# Volt_Metter_SCH.net
KiCad netlist of a schematic drawn in Altium Designer
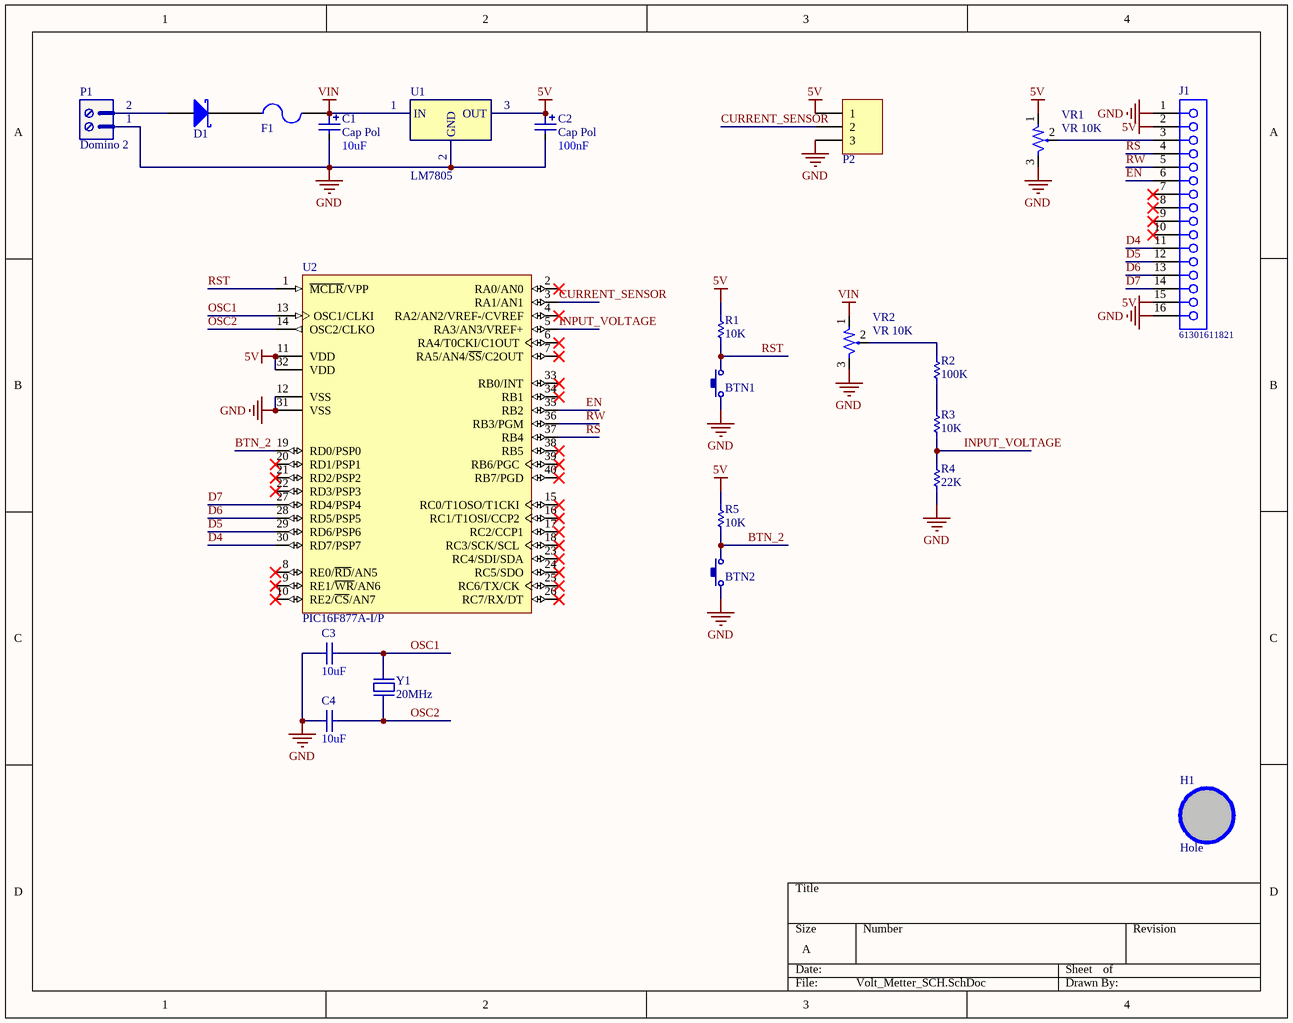
[diagram p0: Volt_Metter_SCH.SchDoc]

(export (version "E")
  (design (tool "Eeschema 10.0.6"))
  (components
    (comp (ref "BTN1")
      (value "Button")
      (footprint "Button")
      (libsource (lib "DeltaCross_Lib") (part "Button"))
    )
    (comp (ref "BTN2")
      (value "Button")
      (footprint "Button")
      (libsource (lib "DeltaCross_Lib") (part "Button"))
    )
    (comp (ref "C1")
      (value "Cap Pol")
      (footprint "CP1/2.5")
      (description "Polarized Capacitor (Radial)")
      (fields (field (name "ALTIUM_VALUE") "10uF"))
      (libsource (lib "DeltaCross_Lib") (part "Cap Pol"))
    )
    (comp (ref "C2")
      (value "Cap Pol")
      (footprint "CP1/2.5")
      (description "Polarized Capacitor (Radial)")
      (fields (field (name "ALTIUM_VALUE") "100nF"))
      (libsource (lib "DeltaCross_Lib") (part "Cap Pol"))
    )
    (comp (ref "C3")
      (value "10uF")
      (footprint "CAP-SM-0805")
      (description "Capacitor")
      (fields (field (name "Comment") "Cap Non-Pol SMD"))
      (libsource (lib "DeltaCross_Lib") (part "Cap Non-Pol SMD"))
    )
    (comp (ref "C4")
      (value "10uF")
      (footprint "CAP-SM-0805")
      (description "Capacitor")
      (fields (field (name "Comment") "Cap Non-Pol SMD"))
      (libsource (lib "DeltaCross_Lib") (part "Cap Non-Pol SMD"))
    )
    (comp (ref "D1")
      (value "D Schottky")
      (footprint "SS34")
      (description "Schottky Diode")
      (fields (field (name "PUBLISHER") "Altium Limited"))
      (libsource (lib "PIF_Library") (part "D Schottky"))
    )
    (comp (ref "F1") (value "Fuse") (footprint "FUSE SMD") (libsource (lib "PIF_Library") (part "Fuse")))
    (comp (ref "H1")
      (value "Hole")
      (footprint "LO KHOAN 3MM")
      (description "Hole 3mm")
      (libsource (lib "DeltaCross_Lib") (part "Hole"))
    )
    (comp (ref "J1")
      (value "61301611821")
      (footprint "61301611821")
      (description "WR-PHD Socket Header, THT, pitch 2.54mm, Single Row, Vertical, 16p")
      (fields (field (name "MANUFACTURER") "Wurth Elektronik"))
      (libsource (lib "Altium_WR-PHD (rev20a)") (part "61301611821"))
    )
    (comp (ref "P1")
      (value "Domino 2")
      (footprint "DOMINO 2- 5mm")
      (description "Domino, 2-Pin")
      (fields (field (name "PUBLISHER") "Altium Limited"))
      (libsource (lib "DeltaCross_Lib") (part "Domino 2"))
    )
    (comp (ref "P2")
      (value "Header 3")
      (footprint "JP3")
      (description "Header, 3-Pin")
      (fields (field (name "PUBLISHER") "Altium Limited"))
      (libsource (lib "PIF_Library") (part "Header 3"))
    )
    (comp (ref "R1")
      (value "10K")
      (footprint "RES-SM-0805")
      (fields (field (name "Comment") "Resistor 1/4W"))
      (libsource (lib "DeltaCross_Lib") (part "RES"))
    )
    (comp (ref "R2")
      (value "100K")
      (footprint "RES-SM-0805")
      (fields (field (name "Comment") "Resistor 1/4W"))
      (libsource (lib "DeltaCross_Lib") (part "RES"))
    )
    (comp (ref "R3")
      (value "10K")
      (footprint "RES-SM-0805")
      (fields (field (name "Comment") "Resistor 1/4W"))
      (libsource (lib "DeltaCross_Lib") (part "RES"))
    )
    (comp (ref "R4")
      (value "22K")
      (footprint "RES-SM-0805")
      (fields (field (name "Comment") "Resistor 1/4W"))
      (libsource (lib "DeltaCross_Lib") (part "RES"))
    )
    (comp (ref "R5")
      (value "10K")
      (footprint "RES-SM-0805")
      (fields (field (name "Comment") "Resistor 1/4W"))
      (libsource (lib "DeltaCross_Lib") (part "RES"))
    )
    (comp (ref "U1")
      (value "LM7805")
      (footprint "QTO-220")
      (description "Positive Voltage Regulator")
      (libsource (lib "DeltaCross_Lib") (part "LM7805"))
    )
    (comp (ref "U2")
      (value "PIC16F877A-I/P")
      (footprint "PDIP600-P40")
      (libsource (lib "DeltaCross_Lib") (part "PIC16F877A-I/P"))
    )
    (comp (ref "VR1")
      (value "VR 10K")
      (footprint "Varistor 1")
      (description "Var Resistor")
      (fields (field (name "Comment") "10K"))
      (libsource (lib "PIF_Library") (part "Var Resistor"))
    )
    (comp (ref "VR2")
      (value "VR 10K")
      (footprint "Varistor 1")
      (description "Var Resistor")
      (fields (field (name "Comment") "10K"))
      (libsource (lib "PIF_Library") (part "Var Resistor"))
    )
    (comp (ref "Y1")
      (value "20MHz")
      (footprint "XT2")
      (description "Crystal For all Crystal 2pin")
      (libsource (lib "DeltaCross_Lib") (part "XTAL"))
    )
  )
  (nets
    (net (code "1") (name "/BTN_2") (class "Default")
      (node (ref "BTN2") (pin "2") (pintype "passive"))
      (node (ref "R5") (pin "1") (pintype "passive"))
      (node (ref "U2") (pin "19") (pinfunction "RD0/PSP0_19") (pintype "bidirectional"))
    )
    (net (code "2") (name "/CURRENT_SENSOR") (class "Default")
      (node (ref "P2") (pin "2") (pinfunction "2_2") (pintype "passive"))
      (node (ref "U2") (pin "3") (pinfunction "RA1/AN1_3") (pintype "bidirectional"))
    )
    (net (code "3") (name "/D4") (class "Default")
      (node (ref "J1") (pin "11") (pinfunction "11_11") (pintype "passive"))
      (node (ref "U2") (pin "30") (pinfunction "RD7/PSP7_30") (pintype "bidirectional"))
    )
    (net (code "4") (name "/D5") (class "Default")
      (node (ref "J1") (pin "12") (pinfunction "12_12") (pintype "passive"))
      (node (ref "U2") (pin "29") (pinfunction "RD6/PSP6_29") (pintype "bidirectional"))
    )
    (net (code "5") (name "/D6") (class "Default")
      (node (ref "J1") (pin "13") (pinfunction "13_13") (pintype "passive"))
      (node (ref "U2") (pin "28") (pinfunction "RD5/PSP5_28") (pintype "bidirectional"))
    )
    (net (code "6") (name "/D7") (class "Default")
      (node (ref "J1") (pin "14") (pinfunction "14_14") (pintype "passive"))
      (node (ref "U2") (pin "27") (pinfunction "RD4/PSP4_27") (pintype "bidirectional"))
    )
    (net (code "7") (name "/EN") (class "Default")
      (node (ref "J1") (pin "6") (pinfunction "6_6") (pintype "passive"))
      (node (ref "U2") (pin "35") (pinfunction "RB2_35") (pintype "bidirectional"))
    )
    (net (code "8") (name "/INPUT_VOLTAGE") (class "Default")
      (node (ref "R3") (pin "1") (pintype "passive"))
      (node (ref "R4") (pin "2") (pintype "passive"))
      (node (ref "U2") (pin "5") (pinfunction "RA3/AN3/VREF+_5") (pintype "bidirectional"))
    )
    (net (code "9") (name "/OSC1") (class "Default")
      (node (ref "C3") (pin "2") (pinfunction "2_2") (pintype "passive"))
      (node (ref "U2") (pin "13") (pinfunction "OSC1/CLKI_13") (pintype "input"))
      (node (ref "Y1") (pin "2") (pinfunction "2_2") (pintype "passive"))
    )
    (net (code "10") (name "/OSC2") (class "Default")
      (node (ref "C4") (pin "2") (pinfunction "2_2") (pintype "passive"))
      (node (ref "U2") (pin "14") (pinfunction "OSC2/CLKO_14") (pintype "output"))
      (node (ref "Y1") (pin "1") (pinfunction "1_1") (pintype "passive"))
    )
    (net (code "11") (name "/RS") (class "Default")
      (node (ref "J1") (pin "4") (pinfunction "4_4") (pintype "passive"))
      (node (ref "U2") (pin "37") (pinfunction "RB4_37") (pintype "bidirectional"))
    )
    (net (code "12") (name "/RST") (class "Default")
      (node (ref "BTN1") (pin "2") (pintype "passive"))
      (node (ref "R1") (pin "1") (pintype "passive"))
      (node (ref "U2") (pin "1") (pinfunction "~{MCLR}/VPP_1") (pintype "input"))
    )
    (net (code "13") (name "/RW") (class "Default")
      (node (ref "J1") (pin "5") (pinfunction "5_5") (pintype "passive"))
      (node (ref "U2") (pin "36") (pinfunction "RB3/PGM_36") (pintype "bidirectional"))
    )
    (net (code "14") (name "5V") (class "Default")
      (node (ref "C2") (pin "1") (pinfunction "1_1") (pintype "passive"))
      (node (ref "J1") (pin "15") (pinfunction "15_15") (pintype "passive"))
      (node (ref "J1") (pin "2") (pinfunction "2_2") (pintype "passive"))
      (node (ref "P2") (pin "1") (pinfunction "1_1") (pintype "passive"))
      (node (ref "R1") (pin "2") (pintype "passive"))
      (node (ref "R5") (pin "2") (pintype "passive"))
      (node (ref "U1") (pin "3") (pinfunction "OUT_3") (pintype "power_in"))
      (node (ref "U2") (pin "11") (pinfunction "VDD_11") (pintype "power_in"))
      (node (ref "U2") (pin "32") (pinfunction "VDD_32") (pintype "power_in"))
      (node (ref "VR1") (pin "1") (pinfunction "1_1") (pintype "passive"))
    )
    (net (code "15") (name "GND") (class "Default")
      (node (ref "BTN1") (pin "1") (pintype "passive"))
      (node (ref "BTN2") (pin "1") (pintype "passive"))
      (node (ref "C1") (pin "2") (pinfunction "2_2") (pintype "passive"))
      (node (ref "C2") (pin "2") (pinfunction "2_2") (pintype "passive"))
      (node (ref "C3") (pin "1") (pinfunction "1_1") (pintype "passive"))
      (node (ref "C4") (pin "1") (pinfunction "1_1") (pintype "passive"))
      (node (ref "J1") (pin "1") (pinfunction "1_1") (pintype "passive"))
      (node (ref "J1") (pin "16") (pinfunction "16_16") (pintype "passive"))
      (node (ref "P1") (pin "1") (pinfunction "1_1") (pintype "passive"))
      (node (ref "P2") (pin "3") (pinfunction "3_3") (pintype "passive"))
      (node (ref "R4") (pin "1") (pintype "passive"))
      (node (ref "U1") (pin "2") (pinfunction "GND_2") (pintype "power_in"))
      (node (ref "U2") (pin "12") (pinfunction "VSS_12") (pintype "power_in"))
      (node (ref "U2") (pin "31") (pinfunction "VSS_31") (pintype "power_in"))
      (node (ref "VR1") (pin "3") (pinfunction "3_3") (pintype "passive"))
      (node (ref "VR2") (pin "3") (pinfunction "3_3") (pintype "passive"))
    )
    (net (code "16") (name "Net-(D1-A)") (class "Default")
      (node (ref "D1") (pin "1") (pinfunction "A_1") (pintype "passive"))
      (node (ref "P1") (pin "2") (pinfunction "2_2") (pintype "passive"))
    )
    (net (code "17") (name "Net-(D1-K)") (class "Default")
      (node (ref "D1") (pin "2") (pinfunction "K_2") (pintype "passive"))
      (node (ref "F1") (pin "1") (pinfunction "1_1") (pintype "passive"))
    )
    (net (code "18") (name "Net-(J1-Pad3)") (class "Default")
      (node (ref "J1") (pin "3") (pinfunction "3_3") (pintype "passive"))
      (node (ref "VR1") (pin "2") (pinfunction "2_2") (pintype "passive"))
    )
    (net (code "19") (name "Net-(R2-Pad1)") (class "Default")
      (node (ref "R2") (pin "1") (pintype "passive"))
      (node (ref "R3") (pin "2") (pintype "passive"))
    )
    (net (code "20") (name "Net-(R2-Pad2)") (class "Default")
      (node (ref "R2") (pin "2") (pintype "passive"))
      (node (ref "VR2") (pin "2") (pinfunction "2_2") (pintype "passive"))
    )
    (net (code "21") (name "VIN") (class "Default")
      (node (ref "C1") (pin "1") (pinfunction "1_1") (pintype "passive"))
      (node (ref "F1") (pin "2") (pinfunction "2_2") (pintype "passive"))
      (node (ref "U1") (pin "1") (pinfunction "IN_1") (pintype "power_in"))
      (node (ref "VR2") (pin "1") (pinfunction "1_1") (pintype "passive"))
    )
    (net (code "22") (name "unconnected-(H1-Pad1)") (class "Default")
      (node (ref "H1") (pin "1") (pinfunction "1_1") (pintype "passive"))
    )
    (net (code "23") (name "unconnected-(J1-Pad7)") (class "Default")
      (node (ref "J1") (pin "7") (pinfunction "7_7") (pintype "passive+no_connect"))
    )
    (net (code "24") (name "unconnected-(J1-Pad8)") (class "Default")
      (node (ref "J1") (pin "8") (pinfunction "8_8") (pintype "passive+no_connect"))
    )
    (net (code "25") (name "unconnected-(J1-Pad9)") (class "Default")
      (node (ref "J1") (pin "9") (pinfunction "9_9") (pintype "passive+no_connect"))
    )
    (net (code "26") (name "unconnected-(J1-Pad10)") (class "Default")
      (node (ref "J1") (pin "10") (pinfunction "10_10") (pintype "passive+no_connect"))
    )
    (net (code "27") (name "unconnected-(U2-RA0{slash}AN0-Pad2)") (class "Default")
      (node (ref "U2") (pin "2") (pinfunction "RA0/AN0_2") (pintype "bidirectional+no_connect"))
    )
    (net (code "28") (name "unconnected-(U2-RA2{slash}AN2{slash}VREF-{slash}CVREF-Pad4)") (class "Default")
      (node (ref "U2") (pin "4") (pinfunction "RA2/AN2/VREF-/CVREF_4") (pintype "bidirectional+no_connect"))
    )
    (net (code "29") (name "unconnected-(U2-RA4{slash}T0CKI{slash}C1OUT-Pad6)") (class "Default")
      (node (ref "U2") (pin "6") (pinfunction "RA4/T0CKI/C1OUT_6") (pintype "bidirectional+no_connect"))
    )
    (net (code "30") (name "unconnected-(U2-RA5{slash}AN4{slash}~{SS}{slash}C2OUT-Pad7)") (class "Default")
      (node (ref "U2") (pin "7") (pinfunction "RA5/AN4/~{SS}/C2OUT_7") (pintype "bidirectional+no_connect"))
    )
    (net (code "31") (name "unconnected-(U2-RB0{slash}INT-Pad33)") (class "Default")
      (node (ref "U2") (pin "33") (pinfunction "RB0/INT_33") (pintype "bidirectional+no_connect"))
    )
    (net (code "32") (name "unconnected-(U2-RB1-Pad34)") (class "Default")
      (node (ref "U2") (pin "34") (pinfunction "RB1_34") (pintype "bidirectional+no_connect"))
    )
    (net (code "33") (name "unconnected-(U2-RB5-Pad38)") (class "Default")
      (node (ref "U2") (pin "38") (pinfunction "RB5_38") (pintype "bidirectional+no_connect"))
    )
    (net (code "34") (name "unconnected-(U2-RB6{slash}PGC-Pad39)") (class "Default")
      (node (ref "U2") (pin "39") (pinfunction "RB6/PGC_39") (pintype "bidirectional+no_connect"))
    )
    (net (code "35") (name "unconnected-(U2-RB7{slash}PGD-Pad40)") (class "Default")
      (node (ref "U2") (pin "40") (pinfunction "RB7/PGD_40") (pintype "bidirectional+no_connect"))
    )
    (net (code "36") (name "unconnected-(U2-RC0{slash}T1OSO{slash}T1CKI-Pad15)") (class "Default")
      (node (ref "U2") (pin "15") (pinfunction "RC0/T1OSO/T1CKI_15") (pintype "bidirectional+no_connect"))
    )
    (net (code "37") (name "unconnected-(U2-RC1{slash}T1OSI{slash}CCP2-Pad16)") (class "Default")
      (node (ref "U2") (pin "16") (pinfunction "RC1/T1OSI/CCP2_16") (pintype "bidirectional+no_connect"))
    )
    (net (code "38") (name "unconnected-(U2-RC2{slash}CCP1-Pad17)") (class "Default")
      (node (ref "U2") (pin "17") (pinfunction "RC2/CCP1_17") (pintype "bidirectional+no_connect"))
    )
    (net (code "39") (name "unconnected-(U2-RC3{slash}SCK{slash}SCL-Pad18)") (class "Default")
      (node (ref "U2") (pin "18") (pinfunction "RC3/SCK/SCL_18") (pintype "bidirectional+no_connect"))
    )
    (net (code "40") (name "unconnected-(U2-RC4{slash}SDI{slash}SDA-Pad23)") (class "Default")
      (node (ref "U2") (pin "23") (pinfunction "RC4/SDI/SDA_23") (pintype "bidirectional+no_connect"))
    )
    (net (code "41") (name "unconnected-(U2-RC5{slash}SDO-Pad24)") (class "Default")
      (node (ref "U2") (pin "24") (pinfunction "RC5/SDO_24") (pintype "bidirectional+no_connect"))
    )
    (net (code "42") (name "unconnected-(U2-RC6{slash}TX{slash}CK-Pad25)") (class "Default")
      (node (ref "U2") (pin "25") (pinfunction "RC6/TX/CK_25") (pintype "bidirectional+no_connect"))
    )
    (net (code "43") (name "unconnected-(U2-RC7{slash}RX{slash}DT-Pad26)") (class "Default")
      (node (ref "U2") (pin "26") (pinfunction "RC7/RX/DT_26") (pintype "bidirectional+no_connect"))
    )
    (net (code "44") (name "unconnected-(U2-RD1{slash}PSP1-Pad20)") (class "Default")
      (node (ref "U2") (pin "20") (pinfunction "RD1/PSP1_20") (pintype "bidirectional+no_connect"))
    )
    (net (code "45") (name "unconnected-(U2-RD2{slash}PSP2-Pad21)") (class "Default")
      (node (ref "U2") (pin "21") (pinfunction "RD2/PSP2_21") (pintype "bidirectional+no_connect"))
    )
    (net (code "46") (name "unconnected-(U2-RD3{slash}PSP3-Pad22)") (class "Default")
      (node (ref "U2") (pin "22") (pinfunction "RD3/PSP3_22") (pintype "bidirectional+no_connect"))
    )
    (net (code "47") (name "unconnected-(U2-RE0{slash}~{RD}{slash}AN5-Pad8)") (class "Default")
      (node (ref "U2") (pin "8") (pinfunction "RE0/~{RD}/AN5_8") (pintype "bidirectional+no_connect"))
    )
    (net (code "48") (name "unconnected-(U2-RE1{slash}~{WR}{slash}AN6-Pad9)") (class "Default")
      (node (ref "U2") (pin "9") (pinfunction "RE1/~{WR}/AN6_9") (pintype "bidirectional+no_connect"))
    )
    (net (code "49") (name "unconnected-(U2-RE2{slash}~{CS}{slash}AN7-Pad10)") (class "Default")
      (node (ref "U2") (pin "10") (pinfunction "RE2/~{CS}/AN7_10") (pintype "bidirectional+no_connect"))
    )
  )
)
